# Sub_Board.net
KiCad netlist of a schematic drawn in EAGLE
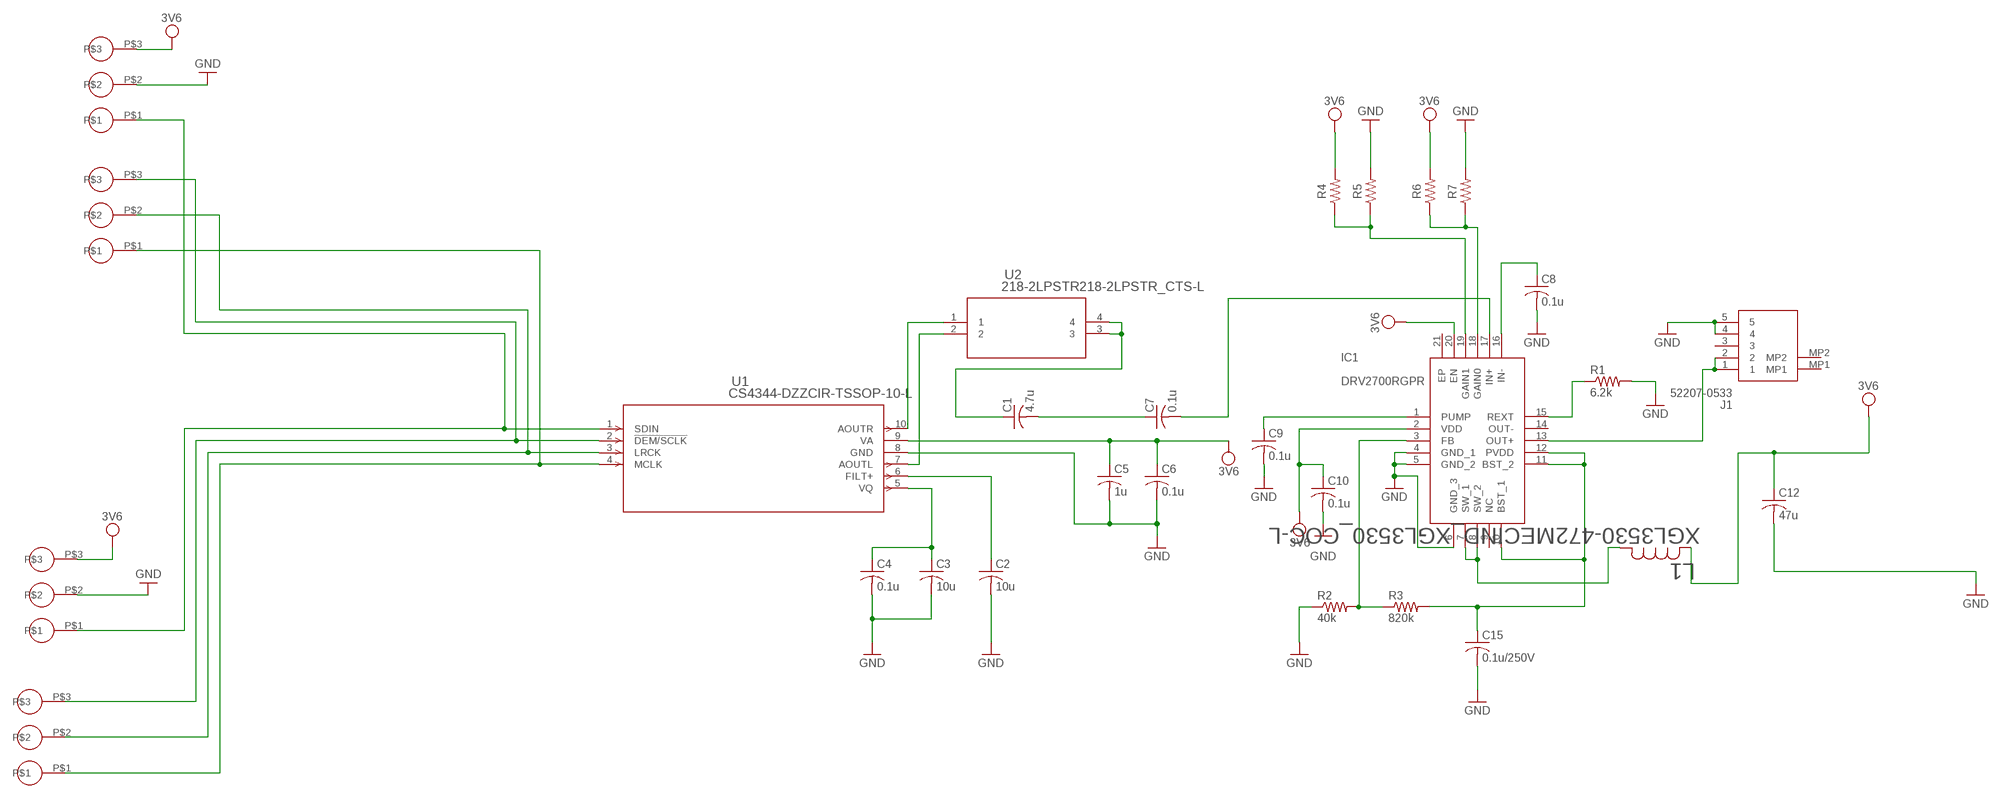
[diagram p0: schematic, sheet 1]

(export (version "E")
  (design (tool "Eeschema 10.0.6"))
  (components
    (comp (ref "C1")
      (value "4.7u")
      (footprint "eagle-import:CAPC1608X85")
      (libsource (lib "eagle-import") (part "C-USCHIP-0603(1608-METRIC)_"))
    )
    (comp (ref "C2")
      (value "10u")
      (footprint "eagle-import:CAPC1608X85")
      (libsource (lib "eagle-import") (part "C-USCHIP-0603(1608-METRIC)_"))
    )
    (comp (ref "C3")
      (value "10u")
      (footprint "eagle-import:CAPC1608X85")
      (libsource (lib "eagle-import") (part "C-USCHIP-0603(1608-METRIC)_"))
    )
    (comp (ref "C4")
      (value "0.1u")
      (footprint "eagle-import:CAPC1608X85")
      (libsource (lib "eagle-import") (part "C-USCHIP-0603(1608-METRIC)_"))
    )
    (comp (ref "C5")
      (value "1u")
      (footprint "eagle-import:CAPC1608X85")
      (libsource (lib "eagle-import") (part "C-USCHIP-0603(1608-METRIC)_"))
    )
    (comp (ref "C6")
      (value "0.1u")
      (footprint "eagle-import:CAPC1608X85")
      (libsource (lib "eagle-import") (part "C-USCHIP-0603(1608-METRIC)_"))
    )
    (comp (ref "C7")
      (value "0.1u")
      (footprint "eagle-import:CAPC1608X85")
      (libsource (lib "eagle-import") (part "C-USCHIP-0603(1608-METRIC)_"))
    )
    (comp (ref "C8")
      (value "0.1u")
      (footprint "eagle-import:CAPC1608X85")
      (libsource (lib "eagle-import") (part "C-USCHIP-0603(1608-METRIC)_"))
    )
    (comp (ref "C9")
      (value "0.1u")
      (footprint "eagle-import:CAPC1608X85")
      (libsource (lib "eagle-import") (part "C-USCHIP-0603(1608-METRIC)_"))
    )
    (comp (ref "C10")
      (value "0.1u")
      (footprint "eagle-import:CAPC1608X85")
      (libsource (lib "eagle-import") (part "C-USCHIP-0603(1608-METRIC)_"))
    )
    (comp (ref "C12")
      (value "47u")
      (footprint "eagle-import:CAPC1608X85")
      (libsource (lib "eagle-import") (part "C-USCHIP-0603(1608-METRIC)_"))
    )
    (comp (ref "C15")
      (value "0.1u/250V")
      (footprint "eagle-import:CAPC3216X135")
      (libsource (lib "eagle-import") (part "C-USCHIP-1206(3216-METRIC)_"))
    )
    (comp (ref "IC1")
      (value "DRV2700RGPR")
      (footprint "eagle-import:QFN50P400X400X100-21N")
      (fields (field (name "MOUSER_PART_NUMBER") "595-DRV2700RGPR"))
      (libsource (lib "eagle-import") (part "DRV2700RGPR"))
    )
    (comp (ref "J1")
      (value "52207-0533")
      (footprint "eagle-import:522070533")
      (fields (field (name "MOUSER_PART_NUMBER") "538-52207-0533"))
      (libsource (lib "eagle-import") (part "52207-0533"))
    )
    (comp (ref "L1")
      (value "XGL3530-472MECIND_XGL3530_COC-L")
      (footprint "eagle-import:IND_XGL3530_COC-L")
      (fields
        (field (name "MANUFACTURER_PART_NUMBER") "XGL3530-472MEC")
        (field (name "COPYRIGHT") "Copyright (C) 2024 Ultra Librarian. All rights reserved.")
      )
      (libsource (lib "eagle-import") (part "XGL3530-472MECIND_XGL3530_COC-L"))
    )
    (comp (ref "R1")
      (value "6.2k")
      (footprint "eagle-import:RESC1608X60")
      (libsource (lib "eagle-import") (part "Tutorial - Fusion 360_16997205_R-USCHIP-0603(1608-METRIC)_"))
    )
    (comp (ref "R2")
      (value "40k")
      (footprint "eagle-import:RESC1608X60")
      (libsource (lib "eagle-import") (part "Tutorial - Fusion 360_16997205_R-USCHIP-0603(1608-METRIC)_"))
    )
    (comp (ref "R3")
      (value "820k")
      (footprint "eagle-import:RESC1608X60")
      (libsource (lib "eagle-import") (part "Tutorial - Fusion 360_16997205_R-USCHIP-0603(1608-METRIC)_"))
    )
    (comp (ref "R4")
      (value "R-US_CHIP-0603(1608-METRIC)")
      (footprint "eagle-import:RESC1608X60")
      (libsource (lib "eagle-import") (part "R-USCHIP-0603(1608-METRIC)_"))
    )
    (comp (ref "R5")
      (value "R-US_CHIP-0603(1608-METRIC)")
      (footprint "eagle-import:RESC1608X60")
      (libsource (lib "eagle-import") (part "R-USCHIP-0603(1608-METRIC)_"))
    )
    (comp (ref "R6")
      (value "R-US_CHIP-0603(1608-METRIC)")
      (footprint "eagle-import:RESC1608X60")
      (libsource (lib "eagle-import") (part "R-USCHIP-0603(1608-METRIC)_"))
    )
    (comp (ref "R7")
      (value "R-US_CHIP-0603(1608-METRIC)")
      (footprint "eagle-import:RESC1608X60")
      (libsource (lib "eagle-import") (part "R-USCHIP-0603(1608-METRIC)_"))
    )
    (comp (ref "U$1")
      (value "CONECTOR_MEM")
      (footprint "eagle-import:CONECTOR_MEM")
      (libsource (lib "eagle-import") (part "CONECTOR_MEM"))
    )
    (comp (ref "U$2")
      (value "CONECTOR_MEM")
      (footprint "eagle-import:CONECTOR_MEM")
      (libsource (lib "eagle-import") (part "CONECTOR_MEM"))
    )
    (comp (ref "U$3")
      (value "CONECTOR_MEM")
      (footprint "eagle-import:CONECTOR_MEM")
      (libsource (lib "eagle-import") (part "CONECTOR_MEM"))
    )
    (comp (ref "U$4")
      (value "CONECTOR_MEM")
      (footprint "eagle-import:CONECTOR_MEM")
      (libsource (lib "eagle-import") (part "CONECTOR_MEM"))
    )
    (comp (ref "U1")
      (value "CS4344-DZZCIR-TSSOP-10-L")
      (footprint "eagle-import:CIR-TSSOP-10-L")
      (fields
        (field (name "MANUFACTURER_PART_NUMBER") "CS4344-DZZ")
        (field (name "COPYRIGHT") "Copyright (C) 2024 Ultra Librarian. All rights reserved.")
      )
      (libsource (lib "eagle-import") (part "CS4344-DZZCIR-TSSOP-10-L"))
    )
    (comp (ref "U2")
      (value "218-2LPSTR218-2LPSTR_CTS-L")
      (footprint "eagle-import:218-2LPSTR_CTS-L")
      (fields
        (field (name "MANUFACTURER_PART_NUMBER") "218-2LPSTR")
        (field (name "COPYRIGHT") "Copyright (C) 2024 Ultra Librarian. All rights reserved.")
      )
      (libsource (lib "eagle-import") (part "218-2LPSTR218-2LPSTR_CTS-L"))
    )
  )
  (nets
    (net (code "1") (name "3V6") (class "Default")
      (node (ref "C10") (pin "1") (pinfunction "1_1") (pintype "passive"))
      (node (ref "C12") (pin "1") (pinfunction "1_1") (pintype "passive"))
      (node (ref "C5") (pin "1") (pinfunction "1_1") (pintype "passive"))
      (node (ref "C6") (pin "1") (pinfunction "1_1") (pintype "passive"))
      (node (ref "IC1") (pin "2") (pinfunction "VDD_2") (pintype "bidirectional"))
      (node (ref "IC1") (pin "20") (pinfunction "EN_20") (pintype "bidirectional"))
      (node (ref "L1") (pin "2") (pinfunction "2_2") (pintype "passive"))
      (node (ref "R4") (pin "2") (pinfunction "2_2") (pintype "passive"))
      (node (ref "R6") (pin "2") (pinfunction "2_2") (pintype "passive"))
      (node (ref "U$1") (pin "P$3") (pinfunction "P$3_P$3") (pintype "bidirectional"))
      (node (ref "U$3") (pin "P$3") (pinfunction "P$3_P$3") (pintype "bidirectional"))
      (node (ref "U1") (pin "9") (pinfunction "VA_9") (pintype "power_in"))
    )
    (net (code "2") (name "GND") (class "Default")
      (node (ref "C10") (pin "2") (pinfunction "2_2") (pintype "passive"))
      (node (ref "C12") (pin "2") (pinfunction "2_2") (pintype "passive"))
      (node (ref "C15") (pin "2") (pinfunction "2_2") (pintype "passive"))
      (node (ref "C2") (pin "2") (pinfunction "2_2") (pintype "passive"))
      (node (ref "C3") (pin "2") (pinfunction "2_2") (pintype "passive"))
      (node (ref "C4") (pin "2") (pinfunction "2_2") (pintype "passive"))
      (node (ref "C5") (pin "2") (pinfunction "2_2") (pintype "passive"))
      (node (ref "C6") (pin "2") (pinfunction "2_2") (pintype "passive"))
      (node (ref "C8") (pin "2") (pinfunction "2_2") (pintype "passive"))
      (node (ref "C9") (pin "2") (pinfunction "2_2") (pintype "passive"))
      (node (ref "IC1") (pin "4") (pinfunction "GND_1_4") (pintype "bidirectional"))
      (node (ref "IC1") (pin "5") (pinfunction "GND_2_5") (pintype "bidirectional"))
      (node (ref "IC1") (pin "6") (pinfunction "GND_3_6") (pintype "bidirectional"))
      (node (ref "J1") (pin "4") (pinfunction "4_4") (pintype "bidirectional"))
      (node (ref "J1") (pin "5") (pinfunction "5_5") (pintype "bidirectional"))
      (node (ref "R1") (pin "2") (pinfunction "2_2") (pintype "passive"))
      (node (ref "R2") (pin "1") (pinfunction "1_1") (pintype "passive"))
      (node (ref "R5") (pin "2") (pinfunction "2_2") (pintype "passive"))
      (node (ref "R7") (pin "2") (pinfunction "2_2") (pintype "passive"))
      (node (ref "U$1") (pin "P$2") (pinfunction "P$2_P$2") (pintype "bidirectional"))
      (node (ref "U$3") (pin "P$2") (pinfunction "P$2_P$2") (pintype "bidirectional"))
      (node (ref "U1") (pin "8") (pinfunction "GND_8") (pintype "power_in"))
    )
    (net (code "3") (name "Net-(C1-Pad1)") (class "Default")
      (node (ref "C1") (pin "1") (pinfunction "1_1") (pintype "passive"))
      (node (ref "U2") (pin "3") (pinfunction "3_3") (pintype "passive"))
      (node (ref "U2") (pin "4") (pinfunction "4_4") (pintype "passive"))
    )
    (net (code "4") (name "Net-(C1-Pad2)") (class "Default")
      (node (ref "C1") (pin "2") (pinfunction "2_2") (pintype "passive"))
      (node (ref "C7") (pin "1") (pinfunction "1_1") (pintype "passive"))
    )
    (net (code "5") (name "Net-(IC1-BST_1)") (class "Default")
      (node (ref "C15") (pin "1") (pinfunction "1_1") (pintype "passive"))
      (node (ref "IC1") (pin "10") (pinfunction "BST_1_10") (pintype "bidirectional"))
      (node (ref "IC1") (pin "11") (pinfunction "BST_2_11") (pintype "bidirectional"))
      (node (ref "IC1") (pin "12") (pinfunction "PVDD_12") (pintype "bidirectional"))
      (node (ref "R3") (pin "2") (pinfunction "2_2") (pintype "passive"))
    )
    (net (code "6") (name "Net-(IC1-FB)") (class "Default")
      (node (ref "IC1") (pin "3") (pinfunction "FB_3") (pintype "bidirectional"))
      (node (ref "R2") (pin "2") (pinfunction "2_2") (pintype "passive"))
      (node (ref "R3") (pin "1") (pinfunction "1_1") (pintype "passive"))
    )
    (net (code "7") (name "Net-(IC1-GAIN0)") (class "Default")
      (node (ref "IC1") (pin "18") (pinfunction "GAIN0_18") (pintype "bidirectional"))
      (node (ref "R6") (pin "1") (pinfunction "1_1") (pintype "passive"))
      (node (ref "R7") (pin "1") (pinfunction "1_1") (pintype "passive"))
    )
    (net (code "8") (name "Net-(IC1-GAIN1)") (class "Default")
      (node (ref "IC1") (pin "19") (pinfunction "GAIN1_19") (pintype "bidirectional"))
      (node (ref "R4") (pin "1") (pinfunction "1_1") (pintype "passive"))
      (node (ref "R5") (pin "1") (pinfunction "1_1") (pintype "passive"))
    )
    (net (code "9") (name "Net-(IC1-IN+)") (class "Default")
      (node (ref "C7") (pin "2") (pinfunction "2_2") (pintype "passive"))
      (node (ref "IC1") (pin "17") (pinfunction "IN+_17") (pintype "bidirectional"))
    )
    (net (code "10") (name "Net-(IC1-IN-)") (class "Default")
      (node (ref "C8") (pin "1") (pinfunction "1_1") (pintype "passive"))
      (node (ref "IC1") (pin "16") (pinfunction "IN-_16") (pintype "bidirectional"))
    )
    (net (code "11") (name "Net-(IC1-OUT+)") (class "Default")
      (node (ref "IC1") (pin "13") (pinfunction "OUT+_13") (pintype "bidirectional"))
      (node (ref "J1") (pin "1") (pinfunction "1_1") (pintype "bidirectional"))
      (node (ref "J1") (pin "2") (pinfunction "2_2") (pintype "bidirectional"))
    )
    (net (code "12") (name "Net-(IC1-PUMP)") (class "Default")
      (node (ref "C9") (pin "1") (pinfunction "1_1") (pintype "passive"))
      (node (ref "IC1") (pin "1") (pinfunction "PUMP_1") (pintype "bidirectional"))
    )
    (net (code "13") (name "Net-(IC1-REXT)") (class "Default")
      (node (ref "IC1") (pin "15") (pinfunction "REXT_15") (pintype "bidirectional"))
      (node (ref "R1") (pin "1") (pinfunction "1_1") (pintype "passive"))
    )
    (net (code "14") (name "Net-(IC1-SW_1)") (class "Default")
      (node (ref "IC1") (pin "7") (pinfunction "SW_1_7") (pintype "bidirectional"))
      (node (ref "IC1") (pin "8") (pinfunction "SW_2_8") (pintype "bidirectional"))
      (node (ref "L1") (pin "1") (pinfunction "1_1") (pintype "passive"))
    )
    (net (code "15") (name "Net-(U1-AOUTL)") (class "Default")
      (node (ref "U1") (pin "7") (pinfunction "AOUTL_7") (pintype "output"))
      (node (ref "U2") (pin "2") (pinfunction "2_2") (pintype "passive"))
    )
    (net (code "16") (name "Net-(U1-AOUTR)") (class "Default")
      (node (ref "U1") (pin "10") (pinfunction "AOUTR_10") (pintype "output"))
      (node (ref "U2") (pin "1") (pinfunction "1_1") (pintype "passive"))
    )
    (net (code "17") (name "Net-(U1-FILT+)") (class "Default")
      (node (ref "C2") (pin "1") (pinfunction "1_1") (pintype "passive"))
      (node (ref "U1") (pin "6") (pinfunction "FILT+_6") (pintype "output"))
    )
    (net (code "18") (name "Net-(U1-LRCK)") (class "Default")
      (node (ref "U$2") (pin "P$2") (pinfunction "P$2_P$2") (pintype "bidirectional"))
      (node (ref "U$4") (pin "P$2") (pinfunction "P$2_P$2") (pintype "bidirectional"))
      (node (ref "U1") (pin "3") (pinfunction "LRCK_3") (pintype "input"))
    )
    (net (code "19") (name "Net-(U1-MCLK)") (class "Default")
      (node (ref "U$2") (pin "P$1") (pinfunction "P$1_P$1") (pintype "bidirectional"))
      (node (ref "U$4") (pin "P$1") (pinfunction "P$1_P$1") (pintype "bidirectional"))
      (node (ref "U1") (pin "4") (pinfunction "MCLK_4") (pintype "input"))
    )
    (net (code "20") (name "Net-(U1-SDIN)") (class "Default")
      (node (ref "U$1") (pin "P$1") (pinfunction "P$1_P$1") (pintype "bidirectional"))
      (node (ref "U$3") (pin "P$1") (pinfunction "P$1_P$1") (pintype "bidirectional"))
      (node (ref "U1") (pin "1") (pinfunction "SDIN_1") (pintype "input"))
    )
    (net (code "21") (name "Net-(U1-VQ)") (class "Default")
      (node (ref "C3") (pin "1") (pinfunction "1_1") (pintype "passive"))
      (node (ref "C4") (pin "1") (pinfunction "1_1") (pintype "passive"))
      (node (ref "U1") (pin "5") (pinfunction "VQ_5") (pintype "output"))
    )
    (net (code "22") (name "Net-(U1-~{DEM{slash}SCLK})") (class "Default")
      (node (ref "U$2") (pin "P$3") (pinfunction "P$3_P$3") (pintype "bidirectional"))
      (node (ref "U$4") (pin "P$3") (pinfunction "P$3_P$3") (pintype "bidirectional"))
      (node (ref "U1") (pin "2") (pinfunction "~{DEM/SCLK}_2") (pintype "input"))
    )
    (net (code "23") (name "unconnected-(IC1-EP-Pad21)") (class "Default")
      (node (ref "IC1") (pin "21") (pinfunction "EP_21") (pintype "bidirectional"))
    )
    (net (code "24") (name "unconnected-(IC1-NC-Pad9)") (class "Default")
      (node (ref "IC1") (pin "9") (pinfunction "NC_9") (pintype "no_connect"))
    )
    (net (code "25") (name "unconnected-(IC1-OUT--Pad14)") (class "Default")
      (node (ref "IC1") (pin "14") (pinfunction "OUT-_14") (pintype "bidirectional"))
    )
    (net (code "26") (name "unconnected-(J1-Pad3)") (class "Default")
      (node (ref "J1") (pin "3") (pinfunction "3_3") (pintype "bidirectional"))
    )
    (net (code "27") (name "unconnected-(J1-PadMP1)") (class "Default")
      (node (ref "J1") (pin "MP1") (pinfunction "MP1_MP1") (pintype "bidirectional"))
    )
    (net (code "28") (name "unconnected-(J1-PadMP2)") (class "Default")
      (node (ref "J1") (pin "MP2") (pinfunction "MP2_MP2") (pintype "bidirectional"))
    )
  )
)
